# main_2_0.net
KiCad netlist of a schematic drawn in EAGLE
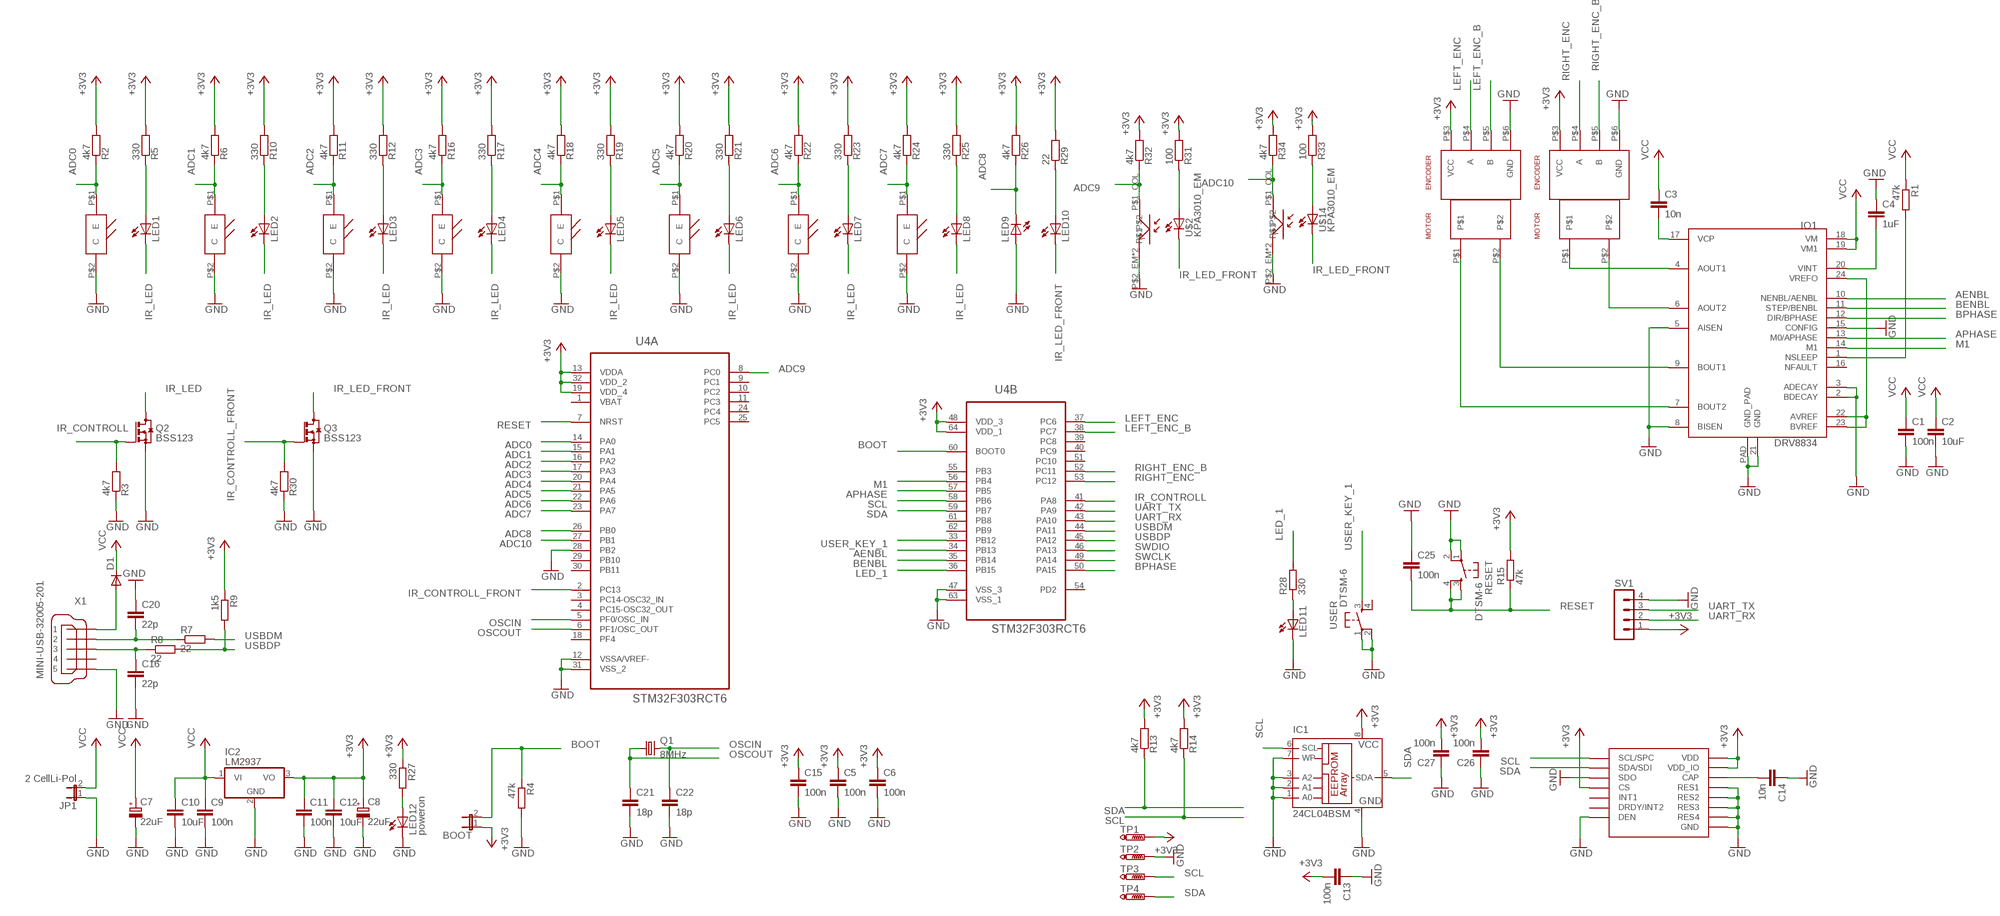
[diagram p0: schematic, sheet 1]

(export (version "E")
  (design (tool "Eeschema 10.0.6"))
  (components
    (comp (ref "BOOT")
      (value "JP1E")
      (footprint "eagle-import:JP1")
      (libsource (lib "eagle-import") (part "JP1E"))
    )
    (comp (ref "C1")
      (value "100n")
      (footprint "eagle-import:C1206")
      (libsource (lib "eagle-import") (part "C-EUC1206"))
    )
    (comp (ref "C2")
      (value "10uF")
      (footprint "eagle-import:C1206")
      (libsource (lib "eagle-import") (part "C-EUC1206"))
    )
    (comp (ref "C3")
      (value "10n")
      (footprint "eagle-import:C1206")
      (libsource (lib "eagle-import") (part "C-EUC1206"))
    )
    (comp (ref "C4")
      (value "1uF")
      (footprint "eagle-import:C1206")
      (libsource (lib "eagle-import") (part "C-EUC1206"))
    )
    (comp (ref "C5")
      (value "100n")
      (footprint "eagle-import:C0805")
      (libsource (lib "eagle-import") (part "C-EUC0805"))
    )
    (comp (ref "C6")
      (value "100n")
      (footprint "eagle-import:C0805")
      (libsource (lib "eagle-import") (part "C-EUC0805"))
    )
    (comp (ref "C7")
      (value "22uF")
      (footprint "eagle-import:153CLV-0505")
      (libsource (lib "eagle-import") (part "CPOL-EU153CLV-0505"))
    )
    (comp (ref "C8")
      (value "22uF")
      (footprint "eagle-import:153CLV-0505")
      (libsource (lib "eagle-import") (part "CPOL-EU153CLV-0505"))
    )
    (comp (ref "C9")
      (value "100n")
      (footprint "eagle-import:C0805")
      (libsource (lib "eagle-import") (part "C-EUC0805"))
    )
    (comp (ref "C10")
      (value "10uF")
      (footprint "eagle-import:C0805")
      (libsource (lib "eagle-import") (part "C-EUC0805"))
    )
    (comp (ref "C11")
      (value "100n")
      (footprint "eagle-import:C0805")
      (libsource (lib "eagle-import") (part "C-EUC0805"))
    )
    (comp (ref "C12")
      (value "10uF")
      (footprint "eagle-import:C0805")
      (libsource (lib "eagle-import") (part "C-EUC0805"))
    )
    (comp (ref "C13")
      (value "100n")
      (footprint "eagle-import:C0805")
      (libsource (lib "eagle-import") (part "C-EUC0805"))
    )
    (comp (ref "C14")
      (value "10n")
      (footprint "eagle-import:C0805")
      (libsource (lib "eagle-import") (part "C-EUC0805"))
    )
    (comp (ref "C15")
      (value "100n")
      (footprint "eagle-import:C0805")
      (libsource (lib "eagle-import") (part "C-EUC0805"))
    )
    (comp (ref "C16")
      (value "22p")
      (footprint "eagle-import:C0805")
      (libsource (lib "eagle-import") (part "C-EUC0805"))
    )
    (comp (ref "C20")
      (value "22p")
      (footprint "eagle-import:C0805")
      (libsource (lib "eagle-import") (part "C-EUC0805"))
    )
    (comp (ref "C21")
      (value "18p")
      (footprint "eagle-import:C0805")
      (libsource (lib "eagle-import") (part "C-EUC0805"))
    )
    (comp (ref "C22")
      (value "18p")
      (footprint "eagle-import:C0805")
      (libsource (lib "eagle-import") (part "C-EUC0805"))
    )
    (comp (ref "C25")
      (value "100n")
      (footprint "eagle-import:C0805")
      (libsource (lib "eagle-import") (part "C-EUC0805"))
    )
    (comp (ref "C26")
      (value "100n")
      (footprint "eagle-import:C0805")
      (libsource (lib "eagle-import") (part "C-EUC0805"))
    )
    (comp (ref "C27")
      (value "100n")
      (footprint "eagle-import:C0805")
      (libsource (lib "eagle-import") (part "C-EUC0805"))
    )
    (comp (ref "D1")
      (value "DIODE-SMB")
      (footprint "eagle-import:SMB")
      (libsource (lib "eagle-import") (part "DIODE-SMB"))
    )
    (comp (ref "IC1")
      (value "24CL04BSM")
      (footprint "eagle-import:SO-08M")
      (fields (field (name "MPN") "FM24CL04-S"))
      (libsource (lib "eagle-import") (part "24SMCL04B"))
    )
    (comp (ref "IC2")
      (value "LM2937")
      (footprint "eagle-import:TO263-3")
      (libsource (lib "eagle-import") (part "LM2937"))
    )
    (comp (ref "IO1")
      (value "DRV8834")
      (footprint "eagle-import:DRV8834_PCK")
      (libsource (lib "eagle-import") (part "DRV8834"))
    )
    (comp (ref "JP1")
      (value "2 CellLi-Pol")
      (footprint "eagle-import:JP1")
      (libsource (lib "eagle-import") (part "JP1E"))
    )
    (comp (ref "LED1")
      (value "LEDCHIPLED_1206")
      (footprint "eagle-import:CHIPLED_1206")
      (libsource (lib "eagle-import") (part "LEDCHIPLED_1206"))
    )
    (comp (ref "LED2")
      (value "LEDCHIPLED_1206")
      (footprint "eagle-import:CHIPLED_1206")
      (libsource (lib "eagle-import") (part "LEDCHIPLED_1206"))
    )
    (comp (ref "LED3")
      (value "LEDCHIPLED_1206")
      (footprint "eagle-import:CHIPLED_1206")
      (libsource (lib "eagle-import") (part "LEDCHIPLED_1206"))
    )
    (comp (ref "LED4")
      (value "LEDCHIPLED_1206")
      (footprint "eagle-import:CHIPLED_1206")
      (libsource (lib "eagle-import") (part "LEDCHIPLED_1206"))
    )
    (comp (ref "LED5")
      (value "LEDCHIPLED_1206")
      (footprint "eagle-import:CHIPLED_1206")
      (libsource (lib "eagle-import") (part "LEDCHIPLED_1206"))
    )
    (comp (ref "LED6")
      (value "LEDCHIPLED_1206")
      (footprint "eagle-import:CHIPLED_1206")
      (libsource (lib "eagle-import") (part "LEDCHIPLED_1206"))
    )
    (comp (ref "LED7")
      (value "LEDCHIPLED_1206")
      (footprint "eagle-import:CHIPLED_1206")
      (libsource (lib "eagle-import") (part "LEDCHIPLED_1206"))
    )
    (comp (ref "LED8")
      (value "LEDCHIPLED_1206")
      (footprint "eagle-import:CHIPLED_1206")
      (libsource (lib "eagle-import") (part "LEDCHIPLED_1206"))
    )
    (comp (ref "LED9")
      (value "LED5MM")
      (footprint "eagle-import:LED5MM")
      (libsource (lib "eagle-import") (part "my_parts_LED5MM"))
    )
    (comp (ref "LED10")
      (value "LED5MM")
      (footprint "eagle-import:LED5MM")
      (libsource (lib "eagle-import") (part "my_parts_LED5MM"))
    )
    (comp (ref "LED11")
      (value "LEDCHIPLED_1206")
      (footprint "eagle-import:CHIPLED_1206")
      (libsource (lib "eagle-import") (part "LEDCHIPLED_1206"))
    )
    (comp (ref "LED12")
      (value "poweron")
      (footprint "eagle-import:CHIPLED_1206")
      (libsource (lib "eagle-import") (part "LEDCHIPLED_1206"))
    )
    (comp (ref "LSM6DS0")
      (value "L3GD20H")
      (footprint "eagle-import:LGA16L")
      (libsource (lib "eagle-import") (part "L3GD20H"))
    )
    (comp (ref "Q1")
      (value "8MHz")
      (footprint "eagle-import:CTS406")
      (libsource (lib "eagle-import") (part "CRYSTALCTS406"))
    )
    (comp (ref "Q2")
      (value "BSS123")
      (footprint "eagle-import:SOT23")
      (libsource (lib "eagle-import") (part "BSS123"))
    )
    (comp (ref "Q3")
      (value "BSS123")
      (footprint "eagle-import:SOT23")
      (libsource (lib "eagle-import") (part "BSS123"))
    )
    (comp (ref "R1")
      (value "47k")
      (footprint "eagle-import:M1206")
      (libsource (lib "eagle-import") (part "R-EU_M1206"))
    )
    (comp (ref "R2")
      (value "4k7")
      (footprint "eagle-import:M0805")
      (libsource (lib "eagle-import") (part "R-EU_M0805"))
    )
    (comp (ref "R3")
      (value "4k7")
      (footprint "eagle-import:M0805")
      (libsource (lib "eagle-import") (part "R-EU_M0805"))
    )
    (comp (ref "R4")
      (value "47k")
      (footprint "eagle-import:M0805")
      (libsource (lib "eagle-import") (part "R-EU_M0805"))
    )
    (comp (ref "R5")
      (value "330")
      (footprint "eagle-import:M0805")
      (libsource (lib "eagle-import") (part "R-EU_M0805"))
    )
    (comp (ref "R6")
      (value "4k7")
      (footprint "eagle-import:M0805")
      (libsource (lib "eagle-import") (part "R-EU_M0805"))
    )
    (comp (ref "R7")
      (value "22")
      (footprint "eagle-import:M0805")
      (libsource (lib "eagle-import") (part "R-EU_M0805"))
    )
    (comp (ref "R8")
      (value "22")
      (footprint "eagle-import:M0805")
      (libsource (lib "eagle-import") (part "R-EU_M0805"))
    )
    (comp (ref "R9")
      (value "1k5")
      (footprint "eagle-import:M0805")
      (libsource (lib "eagle-import") (part "R-EU_M0805"))
    )
    (comp (ref "R10")
      (value "330")
      (footprint "eagle-import:M0805")
      (libsource (lib "eagle-import") (part "R-EU_M0805"))
    )
    (comp (ref "R11")
      (value "4k7")
      (footprint "eagle-import:M0805")
      (libsource (lib "eagle-import") (part "R-EU_M0805"))
    )
    (comp (ref "R12")
      (value "330")
      (footprint "eagle-import:M0805")
      (libsource (lib "eagle-import") (part "R-EU_M0805"))
    )
    (comp (ref "R13")
      (value "4k7")
      (footprint "eagle-import:M0805")
      (libsource (lib "eagle-import") (part "R-EU_M0805"))
    )
    (comp (ref "R14")
      (value "4k7")
      (footprint "eagle-import:M0805")
      (libsource (lib "eagle-import") (part "R-EU_M0805"))
    )
    (comp (ref "R15")
      (value "47k")
      (footprint "eagle-import:M0805")
      (libsource (lib "eagle-import") (part "R-EU_M0805"))
    )
    (comp (ref "R16")
      (value "4k7")
      (footprint "eagle-import:M0805")
      (libsource (lib "eagle-import") (part "R-EU_M0805"))
    )
    (comp (ref "R17")
      (value "330")
      (footprint "eagle-import:M0805")
      (libsource (lib "eagle-import") (part "R-EU_M0805"))
    )
    (comp (ref "R18")
      (value "4k7")
      (footprint "eagle-import:M0805")
      (libsource (lib "eagle-import") (part "R-EU_M0805"))
    )
    (comp (ref "R19")
      (value "330")
      (footprint "eagle-import:M0805")
      (libsource (lib "eagle-import") (part "R-EU_M0805"))
    )
    (comp (ref "R20")
      (value "4k7")
      (footprint "eagle-import:M0805")
      (libsource (lib "eagle-import") (part "R-EU_M0805"))
    )
    (comp (ref "R21")
      (value "330")
      (footprint "eagle-import:M0805")
      (libsource (lib "eagle-import") (part "R-EU_M0805"))
    )
    (comp (ref "R22")
      (value "4k7")
      (footprint "eagle-import:M0805")
      (libsource (lib "eagle-import") (part "R-EU_M0805"))
    )
    (comp (ref "R23")
      (value "330")
      (footprint "eagle-import:M0805")
      (libsource (lib "eagle-import") (part "R-EU_M0805"))
    )
    (comp (ref "R24")
      (value "4k7")
      (footprint "eagle-import:M0805")
      (libsource (lib "eagle-import") (part "R-EU_M0805"))
    )
    (comp (ref "R25")
      (value "330")
      (footprint "eagle-import:M0805")
      (libsource (lib "eagle-import") (part "R-EU_M0805"))
    )
    (comp (ref "R26")
      (value "4k7")
      (footprint "eagle-import:M0805")
      (libsource (lib "eagle-import") (part "R-EU_M0805"))
    )
    (comp (ref "R27")
      (value "330")
      (footprint "eagle-import:M0805")
      (libsource (lib "eagle-import") (part "R-EU_M0805"))
    )
    (comp (ref "R28")
      (value "330")
      (footprint "eagle-import:M0805")
      (libsource (lib "eagle-import") (part "R-EU_M0805"))
    )
    (comp (ref "R29")
      (value "22")
      (footprint "eagle-import:M0805")
      (libsource (lib "eagle-import") (part "R-EU_M0805"))
    )
    (comp (ref "R30")
      (value "4k7")
      (footprint "eagle-import:M0805")
      (libsource (lib "eagle-import") (part "R-EU_M0805"))
    )
    (comp (ref "R31")
      (value "100")
      (footprint "eagle-import:M0805")
      (libsource (lib "eagle-import") (part "R-EU_M0805"))
    )
    (comp (ref "R32")
      (value "4k7")
      (footprint "eagle-import:M0805")
      (libsource (lib "eagle-import") (part "R-EU_M0805"))
    )
    (comp (ref "R33")
      (value "100")
      (footprint "eagle-import:M0805")
      (libsource (lib "eagle-import") (part "R-EU_M0805"))
    )
    (comp (ref "R34")
      (value "4k7")
      (footprint "eagle-import:M0805")
      (libsource (lib "eagle-import") (part "R-EU_M0805"))
    )
    (comp (ref "RESET")
      (value "DTSM-6")
      (footprint "eagle-import:DTSM-6")
      (libsource (lib "eagle-import") (part "DTSM-6"))
    )
    (comp (ref "SV1")
      (value "MA04-1")
      (footprint "eagle-import:MA04-1")
      (libsource (lib "eagle-import") (part "MA04-1"))
    )
    (comp (ref "TP1")
      (value "PTR1B1,27")
      (footprint "eagle-import:B1,27")
      (libsource (lib "eagle-import") (part "PTR1B1,27"))
    )
    (comp (ref "TP2")
      (value "PTR1B1,27")
      (footprint "eagle-import:B1,27")
      (libsource (lib "eagle-import") (part "PTR1B1,27"))
    )
    (comp (ref "TP3")
      (value "PTR1B1,27")
      (footprint "eagle-import:B1,27")
      (libsource (lib "eagle-import") (part "PTR1B1,27"))
    )
    (comp (ref "TP4")
      (value "PTR1B1,27")
      (footprint "eagle-import:B1,27")
      (libsource (lib "eagle-import") (part "PTR1B1,27"))
    )
    (comp (ref "U$1")
      (value "KPA3010")
      (footprint "eagle-import:KPA3010")
      (libsource (lib "eagle-import") (part "KPA3010"))
    )
    (comp (ref "U$2")
      (value "KPA3010_EM")
      (footprint "eagle-import:KPA3010")
      (libsource (lib "eagle-import") (part "KPA3010_EM"))
    )
    (comp (ref "U$3")
      (value "SFH3710")
      (footprint "eagle-import:SFH3710")
      (libsource (lib "eagle-import") (part "SFH3710"))
    )
    (comp (ref "U$4")
      (value "SFH3710")
      (footprint "eagle-import:SFH3710")
      (libsource (lib "eagle-import") (part "SFH3710"))
    )
    (comp (ref "U$5")
      (value "SFH3710")
      (footprint "eagle-import:SFH3710")
      (libsource (lib "eagle-import") (part "SFH3710"))
    )
    (comp (ref "U$6")
      (value "SFH3710")
      (footprint "eagle-import:SFH3710")
      (libsource (lib "eagle-import") (part "SFH3710"))
    )
    (comp (ref "U$7")
      (value "SFH3710")
      (footprint "eagle-import:SFH3710")
      (libsource (lib "eagle-import") (part "SFH3710"))
    )
    (comp (ref "U$8")
      (value "SFH3710")
      (footprint "eagle-import:SFH3710")
      (libsource (lib "eagle-import") (part "SFH3710"))
    )
    (comp (ref "U$9")
      (value "SFH3710")
      (footprint "eagle-import:SFH3710")
      (libsource (lib "eagle-import") (part "SFH3710"))
    )
    (comp (ref "U$10")
      (value "SFH3710")
      (footprint "eagle-import:SFH3710")
      (libsource (lib "eagle-import") (part "SFH3710"))
    )
    (comp (ref "U$11")
      (value "POLOLU_GEAR_MOTORPOLO")
      (footprint "eagle-import:POLOLU_GEAR_MOTOR")
      (libsource (lib "eagle-import") (part "POLOLU_GEAR_MOTORPOLO"))
    )
    (comp (ref "U$12")
      (value "POLOLU_GEAR_MOTORPOLO")
      (footprint "eagle-import:POLOLU_GEAR_MOTOR")
      (libsource (lib "eagle-import") (part "POLOLU_GEAR_MOTORPOLO"))
    )
    (comp (ref "U$13")
      (value "KPA3010")
      (footprint "eagle-import:KPA3010")
      (libsource (lib "eagle-import") (part "KPA3010"))
    )
    (comp (ref "U$14")
      (value "KPA3010_EM")
      (footprint "eagle-import:KPA3010")
      (libsource (lib "eagle-import") (part "KPA3010_EM"))
    )
    (comp (ref "U4")
      (value "STM32F303RCT6")
      (footprint "eagle-import:QFP50P1200X1200X160-64N")
      (libsource (lib "eagle-import") (part "STM32F303RCT6"))
    )
    (comp (ref "USER")
      (value "DTSM-6")
      (footprint "eagle-import:DTSM-6")
      (libsource (lib "eagle-import") (part "DTSM-6"))
    )
    (comp (ref "X1")
      (value "MINI-USB-32005-201")
      (footprint "eagle-import:32005-201")
      (libsource (lib "eagle-import") (part "MINI-USB-32005-201"))
    )
  )
  (nets
    (net (code "1") (name "+3V3") (class "Default")
      (node (ref "BOOT") (pin "1") (pinfunction "1_1") (pintype "passive"))
      (node (ref "C11") (pin "1") (pinfunction "1_1") (pintype "passive"))
      (node (ref "C12") (pin "1") (pinfunction "1_1") (pintype "passive"))
      (node (ref "C13") (pin "2") (pinfunction "2_2") (pintype "passive"))
      (node (ref "C15") (pin "1") (pinfunction "1_1") (pintype "passive"))
      (node (ref "C26") (pin "2") (pinfunction "2_2") (pintype "passive"))
      (node (ref "C27") (pin "2") (pinfunction "2_2") (pintype "passive"))
      (node (ref "C5") (pin "1") (pinfunction "1_1") (pintype "passive"))
      (node (ref "C6") (pin "1") (pinfunction "1_1") (pintype "passive"))
      (node (ref "C8") (pin "+") (pinfunction "+_+") (pintype "passive"))
      (node (ref "IC1") (pin "8") (pinfunction "VCC_8") (pintype "power_in"))
      (node (ref "IC2") (pin "3") (pinfunction "VO_3") (pintype "passive"))
      (node (ref "LSM6DS0") (pin "P$1") (pinfunction "VDD_IO_P$1") (pintype "power_in"))
      (node (ref "LSM6DS0") (pin "P$16") (pinfunction "VDD_P$16") (pintype "power_in"))
      (node (ref "LSM6DS0") (pin "P$5") (pinfunction "CS_P$5") (pintype "bidirectional"))
      (node (ref "R10") (pin "2") (pinfunction "2_2") (pintype "passive"))
      (node (ref "R11") (pin "2") (pinfunction "2_2") (pintype "passive"))
      (node (ref "R12") (pin "2") (pinfunction "2_2") (pintype "passive"))
      (node (ref "R13") (pin "2") (pinfunction "2_2") (pintype "passive"))
      (node (ref "R14") (pin "2") (pinfunction "2_2") (pintype "passive"))
      (node (ref "R15") (pin "2") (pinfunction "2_2") (pintype "passive"))
      (node (ref "R16") (pin "2") (pinfunction "2_2") (pintype "passive"))
      (node (ref "R17") (pin "2") (pinfunction "2_2") (pintype "passive"))
      (node (ref "R18") (pin "2") (pinfunction "2_2") (pintype "passive"))
      (node (ref "R19") (pin "2") (pinfunction "2_2") (pintype "passive"))
      (node (ref "R2") (pin "2") (pinfunction "2_2") (pintype "passive"))
      (node (ref "R20") (pin "2") (pinfunction "2_2") (pintype "passive"))
      (node (ref "R21") (pin "2") (pinfunction "2_2") (pintype "passive"))
      (node (ref "R22") (pin "2") (pinfunction "2_2") (pintype "passive"))
      (node (ref "R23") (pin "2") (pinfunction "2_2") (pintype "passive"))
      (node (ref "R24") (pin "2") (pinfunction "2_2") (pintype "passive"))
      (node (ref "R25") (pin "2") (pinfunction "2_2") (pintype "passive"))
      (node (ref "R26") (pin "2") (pinfunction "2_2") (pintype "passive"))
      (node (ref "R27") (pin "1") (pinfunction "1_1") (pintype "passive"))
      (node (ref "R29") (pin "2") (pinfunction "2_2") (pintype "passive"))
      (node (ref "R31") (pin "2") (pinfunction "2_2") (pintype "passive"))
      (node (ref "R32") (pin "2") (pinfunction "2_2") (pintype "passive"))
      (node (ref "R33") (pin "2") (pinfunction "2_2") (pintype "passive"))
      (node (ref "R34") (pin "2") (pinfunction "2_2") (pintype "passive"))
      (node (ref "R5") (pin "2") (pinfunction "2_2") (pintype "passive"))
      (node (ref "R6") (pin "2") (pinfunction "2_2") (pintype "passive"))
      (node (ref "R9") (pin "1") (pinfunction "1_1") (pintype "passive"))
      (node (ref "SV1") (pin "1") (pinfunction "1_1") (pintype "passive"))
      (node (ref "TP1") (pin "TP") (pinfunction "TP_TP") (pintype "input"))
      (node (ref "U$11") (pin "P$3") (pinfunction "VCC_P$3") (pintype "bidirectional"))
      (node (ref "U$12") (pin "P$3") (pinfunction "VCC_P$3") (pintype "bidirectional"))
      (node (ref "U4") (pin "13") (pinfunction "VDDA_13") (pintype "power_in"))
      (node (ref "U4") (pin "19") (pinfunction "VDD_4_19") (pintype "power_in"))
      (node (ref "U4") (pin "32") (pinfunction "VDD_2_32") (pintype "power_in"))
      (node (ref "U4") (pin "48") (pinfunction "VDD_3_48") (pintype "power_in"))
      (node (ref "U4") (pin "64") (pinfunction "VDD_1_64") (pintype "power_in"))
    )
    (net (code "2") (name "/ADC0") (class "Default")
      (node (ref "R2") (pin "1") (pinfunction "1_1") (pintype "passive"))
      (node (ref "U$3") (pin "P$1") (pinfunction "E_P$1") (pintype "bidirectional"))
      (node (ref "U4") (pin "14") (pinfunction "PA0_14") (pintype "bidirectional"))
    )
    (net (code "3") (name "/ADC1") (class "Default")
      (node (ref "R6") (pin "1") (pinfunction "1_1") (pintype "passive"))
      (node (ref "U$4") (pin "P$1") (pinfunction "E_P$1") (pintype "bidirectional"))
      (node (ref "U4") (pin "15") (pinfunction "PA1_15") (pintype "bidirectional"))
    )
    (net (code "4") (name "/ADC2") (class "Default")
      (node (ref "R11") (pin "1") (pinfunction "1_1") (pintype "passive"))
      (node (ref "U$5") (pin "P$1") (pinfunction "E_P$1") (pintype "bidirectional"))
      (node (ref "U4") (pin "16") (pinfunction "PA2_16") (pintype "bidirectional"))
    )
    (net (code "5") (name "/ADC3") (class "Default")
      (node (ref "R16") (pin "1") (pinfunction "1_1") (pintype "passive"))
      (node (ref "U$6") (pin "P$1") (pinfunction "E_P$1") (pintype "bidirectional"))
      (node (ref "U4") (pin "17") (pinfunction "PA3_17") (pintype "bidirectional"))
    )
    (net (code "6") (name "/ADC4") (class "Default")
      (node (ref "R18") (pin "1") (pinfunction "1_1") (pintype "passive"))
      (node (ref "U$7") (pin "P$1") (pinfunction "E_P$1") (pintype "bidirectional"))
      (node (ref "U4") (pin "20") (pinfunction "PA4_20") (pintype "bidirectional"))
    )
    (net (code "7") (name "/ADC5") (class "Default")
      (node (ref "R20") (pin "1") (pinfunction "1_1") (pintype "passive"))
      (node (ref "U$8") (pin "P$1") (pinfunction "E_P$1") (pintype "bidirectional"))
      (node (ref "U4") (pin "21") (pinfunction "PA5_21") (pintype "bidirectional"))
    )
    (net (code "8") (name "/ADC6") (class "Default")
      (node (ref "R22") (pin "1") (pinfunction "1_1") (pintype "passive"))
      (node (ref "U$9") (pin "P$1") (pinfunction "E_P$1") (pintype "bidirectional"))
      (node (ref "U4") (pin "22") (pinfunction "PA6_22") (pintype "bidirectional"))
    )
    (net (code "9") (name "/ADC7") (class "Default")
      (node (ref "R24") (pin "1") (pinfunction "1_1") (pintype "passive"))
      (node (ref "U$10") (pin "P$1") (pinfunction "E_P$1") (pintype "bidirectional"))
      (node (ref "U4") (pin "23") (pinfunction "PA7_23") (pintype "bidirectional"))
    )
    (net (code "10") (name "/ADC8") (class "Default")
      (node (ref "LED9") (pin "K") (pinfunction "C_K") (pintype "passive"))
      (node (ref "R26") (pin "1") (pinfunction "1_1") (pintype "passive"))
      (node (ref "U4") (pin "26") (pinfunction "PB0_26") (pintype "bidirectional"))
    )
    (net (code "11") (name "/ADC9") (class "Default")
      (node (ref "R32") (pin "1") (pinfunction "1_1") (pintype "passive"))
      (node (ref "U$1") (pin "P$1_COL") (pinfunction "P$1_P$1_COL") (pintype "bidirectional"))
      (node (ref "U4") (pin "8") (pinfunction "PC0_8") (pintype "bidirectional"))
    )
    (net (code "12") (name "/ADC10") (class "Default")
      (node (ref "R34") (pin "1") (pinfunction "1_1") (pintype "passive"))
      (node (ref "U$13") (pin "P$1_COL") (pinfunction "P$1_P$1_COL") (pintype "bidirectional"))
      (node (ref "U4") (pin "27") (pinfunction "PB1_27") (pintype "bidirectional"))
    )
    (net (code "13") (name "/AENBL") (class "Default")
      (node (ref "IO1") (pin "10") (pinfunction "NENBL/AENBL_10") (pintype "bidirectional"))
      (node (ref "U4") (pin "34") (pinfunction "PB13_34") (pintype "bidirectional"))
    )
    (net (code "14") (name "/APHASE") (class "Default")
      (node (ref "IO1") (pin "13") (pinfunction "M0/APHASE_13") (pintype "bidirectional"))
      (node (ref "U4") (pin "57") (pinfunction "PB5_57") (pintype "bidirectional"))
    )
    (net (code "15") (name "/BENBL") (class "Default")
      (node (ref "IO1") (pin "11") (pinfunction "STEP/BENBL_11") (pintype "bidirectional"))
      (node (ref "U4") (pin "35") (pinfunction "PB14_35") (pintype "bidirectional"))
    )
    (net (code "16") (name "/BOOT") (class "Default")
      (node (ref "BOOT") (pin "2") (pinfunction "2_2") (pintype "passive"))
      (node (ref "R4") (pin "1") (pinfunction "1_1") (pintype "passive"))
      (node (ref "U4") (pin "60") (pinfunction "BOOT0_60") (pintype "input"))
    )
    (net (code "17") (name "/BPHASE") (class "Default")
      (node (ref "IO1") (pin "12") (pinfunction "DIR/BPHASE_12") (pintype "bidirectional"))
      (node (ref "U4") (pin "50") (pinfunction "PA15_50") (pintype "bidirectional"))
    )
    (net (code "18") (name "/IR_CONTROLL") (class "Default")
      (node (ref "Q2") (pin "1") (pinfunction "G_1") (pintype "passive"))
      (node (ref "R3") (pin "2") (pinfunction "2_2") (pintype "passive"))
      (node (ref "U4") (pin "41") (pinfunction "PA8_41") (pintype "bidirectional"))
    )
    (net (code "19") (name "/IR_CONTROLL_FRONT") (class "Default")
      (node (ref "Q3") (pin "1") (pinfunction "G_1") (pintype "passive"))
      (node (ref "R30") (pin "2") (pinfunction "2_2") (pintype "passive"))
      (node (ref "U4") (pin "2") (pinfunction "PC13_2") (pintype "bidirectional"))
    )
    (net (code "20") (name "/IR_LED") (class "Default")
      (node (ref "LED1") (pin "C") (pinfunction "C_C") (pintype "passive"))
      (node (ref "LED2") (pin "C") (pinfunction "C_C") (pintype "passive"))
      (node (ref "LED3") (pin "C") (pinfunction "C_C") (pintype "passive"))
      (node (ref "LED4") (pin "C") (pinfunction "C_C") (pintype "passive"))
      (node (ref "LED5") (pin "C") (pinfunction "C_C") (pintype "passive"))
      (node (ref "LED6") (pin "C") (pinfunction "C_C") (pintype "passive"))
      (node (ref "LED7") (pin "C") (pinfunction "C_C") (pintype "passive"))
      (node (ref "LED8") (pin "C") (pinfunction "C_C") (pintype "passive"))
      (node (ref "Q2") (pin "3") (pinfunction "D_3") (pintype "passive"))
    )
    (net (code "21") (name "/IR_LED_FRONT") (class "Default")
      (node (ref "LED10") (pin "K") (pinfunction "C_K") (pintype "passive"))
      (node (ref "Q3") (pin "3") (pinfunction "D_3") (pintype "passive"))
      (node (ref "U$14") (pin "P$1_COL") (pinfunction "C_P$1_COL") (pintype "passive"))
      (node (ref "U$2") (pin "P$1_COL") (pinfunction "C_P$1_COL") (pintype "passive"))
    )
    (net (code "22") (name "/LED_1") (class "Default")
      (node (ref "R28") (pin "2") (pinfunction "2_2") (pintype "passive"))
      (node (ref "U4") (pin "36") (pinfunction "PB15_36") (pintype "bidirectional"))
    )
    (net (code "23") (name "/LEFT_ENC") (class "Default")
      (node (ref "U$11") (pin "P$4") (pinfunction "A_P$4") (pintype "bidirectional"))
      (node (ref "U4") (pin "37") (pinfunction "PC6_37") (pintype "bidirectional"))
    )
    (net (code "24") (name "/LEFT_ENC_B") (class "Default")
      (node (ref "U$11") (pin "P$5") (pinfunction "B_P$5") (pintype "bidirectional"))
      (node (ref "U4") (pin "38") (pinfunction "PC7_38") (pintype "bidirectional"))
    )
    (net (code "25") (name "/M1") (class "Default")
      (node (ref "IO1") (pin "14") (pinfunction "M1_14") (pintype "bidirectional"))
      (node (ref "U4") (pin "56") (pinfunction "PB4_56") (pintype "bidirectional"))
    )
    (net (code "26") (name "/OSCIN") (class "Default")
      (node (ref "C22") (pin "1") (pinfunction "1_1") (pintype "passive"))
      (node (ref "Q1") (pin "3") (pinfunction "2_3") (pintype "passive"))
      (node (ref "U4") (pin "5") (pinfunction "PF0/OSC_IN_5") (pintype "bidirectional"))
    )
    (net (code "27") (name "/OSCOUT") (class "Default")
      (node (ref "C21") (pin "1") (pinfunction "1_1") (pintype "passive"))
      (node (ref "Q1") (pin "1") (pinfunction "1_1") (pintype "passive"))
      (node (ref "U4") (pin "6") (pinfunction "PF1/OSC_OUT_6") (pintype "bidirectional"))
    )
    (net (code "28") (name "/RESET") (class "Default")
      (node (ref "C25") (pin "2") (pinfunction "2_2") (pintype "passive"))
      (node (ref "R15") (pin "1") (pinfunction "1_1") (pintype "passive"))
      (node (ref "RESET") (pin "3") (pinfunction "3_3") (pintype "passive"))
      (node (ref "RESET") (pin "4") (pinfunction "4_4") (pintype "passive"))
      (node (ref "U4") (pin "7") (pinfunction "NRST_7") (pintype "bidirectional"))
    )
    (net (code "29") (name "/RIGHT_ENC") (class "Default")
      (node (ref "U$12") (pin "P$4") (pinfunction "A_P$4") (pintype "bidirectional"))
      (node (ref "U4") (pin "53") (pinfunction "PC12_53") (pintype "bidirectional"))
    )
    (net (code "30") (name "/RIGHT_ENC_B") (class "Default")
      (node (ref "U$12") (pin "P$5") (pinfunction "B_P$5") (pintype "bidirectional"))
      (node (ref "U4") (pin "52") (pinfunction "PC11_52") (pintype "bidirectional"))
    )
    (net (code "31") (name "/SCL") (class "Default")
      (node (ref "IC1") (pin "6") (pinfunction "SCL_6") (pintype "input"))
      (node (ref "LSM6DS0") (pin "P$2") (pinfunction "SCL/SPC_P$2") (pintype "bidirectional"))
      (node (ref "R14") (pin "1") (pinfunction "1_1") (pintype "passive"))
      (node (ref "TP3") (pin "TP") (pinfunction "TP_TP") (pintype "input"))
      (node (ref "U4") (pin "58") (pinfunction "PB6_58") (pintype "bidirectional"))
    )
    (net (code "32") (name "/SDA") (class "Default")
      (node (ref "IC1") (pin "5") (pinfunction "SDA_5") (pintype "bidirectional"))
      (node (ref "LSM6DS0") (pin "P$3") (pinfunction "SDA/SDI_P$3") (pintype "bidirectional"))
      (node (ref "R13") (pin "1") (pinfunction "1_1") (pintype "passive"))
      (node (ref "TP4") (pin "TP") (pinfunction "TP_TP") (pintype "input"))
      (node (ref "U4") (pin "59") (pinfunction "PB7_59") (pintype "bidirectional"))
    )
    (net (code "33") (name "/SWCLK") (class "Default")
      (node (ref "U4") (pin "49") (pinfunction "PA14_49") (pintype "bidirectional"))
    )
    (net (code "34") (name "/SWDIO") (class "Default")
      (node (ref "U4") (pin "46") (pinfunction "PA13_46") (pintype "bidirectional"))
    )
    (net (code "35") (name "/UART_RX") (class "Default")
      (node (ref "SV1") (pin "2") (pinfunction "2_2") (pintype "passive"))
      (node (ref "U4") (pin "43") (pinfunction "PA10_43") (pintype "bidirectional"))
    )
    (net (code "36") (name "/UART_TX") (class "Default")
      (node (ref "SV1") (pin "3") (pinfunction "3_3") (pintype "passive"))
      (node (ref "U4") (pin "42") (pinfunction "PA9_42") (pintype "bidirectional"))
    )
    (net (code "37") (name "/USBDM") (class "Default")
      (node (ref "R7") (pin "2") (pinfunction "2_2") (pintype "passive"))
      (node (ref "U4") (pin "44") (pinfunction "PA11_44") (pintype "bidirectional"))
    )
    (net (code "38") (name "/USBDP") (class "Default")
      (node (ref "R8") (pin "2") (pinfunction "2_2") (pintype "passive"))
      (node (ref "R9") (pin "2") (pinfunction "2_2") (pintype "passive"))
      (node (ref "U4") (pin "45") (pinfunction "PA12_45") (pintype "bidirectional"))
    )
    (net (code "39") (name "/USER_KEY_1") (class "Default")
      (node (ref "U4") (pin "33") (pinfunction "PB12_33") (pintype "bidirectional"))
      (node (ref "USER") (pin "3") (pinfunction "3_3") (pintype "passive"))
    )
    (net (code "40") (name "/VBAT") (class "Default")
      (node (ref "U4") (pin "1") (pinfunction "VBAT_1") (pintype "power_in"))
    )
    (net (code "41") (name "GND") (class "Default")
      (node (ref "C1") (pin "2") (pinfunction "2_2") (pintype "passive"))
      (node (ref "C10") (pin "2") (pinfunction "2_2") (pintype "passive"))
      (node (ref "C11") (pin "2") (pinfunction "2_2") (pintype "passive"))
      (node (ref "C12") (pin "2") (pinfunction "2_2") (pintype "passive"))
      (node (ref "C13") (pin "1") (pinfunction "1_1") (pintype "passive"))
      (node (ref "C14") (pin "1") (pinfunction "1_1") (pintype "passive"))
      (node (ref "C15") (pin "2") (pinfunction "2_2") (pintype "passive"))
      (node (ref "C16") (pin "2") (pinfunction "2_2") (pintype "passive"))
      (node (ref "C2") (pin "2") (pinfunction "2_2") (pintype "passive"))
      (node (ref "C20") (pin "1") (pinfunction "1_1") (pintype "passive"))
      (node (ref "C21") (pin "2") (pinfunction "2_2") (pintype "passive"))
      (node (ref "C22") (pin "2") (pinfunction "2_2") (pintype "passive"))
      (node (ref "C25") (pin "1") (pinfunction "1_1") (pintype "passive"))
      (node (ref "C26") (pin "1") (pinfunction "1_1") (pintype "passive"))
      (node (ref "C27") (pin "1") (pinfunction "1_1") (pintype "passive"))
      (node (ref "C4") (pin "1") (pinfunction "1_1") (pintype "passive"))
      (node (ref "C5") (pin "2") (pinfunction "2_2") (pintype "passive"))
      (node (ref "C6") (pin "2") (pinfunction "2_2") (pintype "passive"))
      (node (ref "C7") (pin "-") (pinfunction "-_-") (pintype "passive"))
      (node (ref "C8") (pin "-") (pinfunction "-_-") (pintype "passive"))
      (node (ref "C9") (pin "2") (pinfunction "2_2") (pintype "passive"))
      (node (ref "IC1") (pin "1") (pinfunction "A0_1") (pintype "input"))
      (node (ref "IC1") (pin "2") (pinfunction "A1_2") (pintype "input"))
      (node (ref "IC1") (pin "3") (pinfunction "A2_3") (pintype "input"))
      (node (ref "IC1") (pin "4") (pinfunction "GND_4") (pintype "power_in"))
      (node (ref "IC1") (pin "7") (pinfunction "WP_7") (pintype "input"))
      (node (ref "IC2") (pin "2") (pinfunction "GND_2") (pintype "passive"))
      (node (ref "IO1") (pin "15") (pinfunction "CONFIG_15") (pintype "bidirectional"))
      (node (ref "IO1") (pin "2") (pinfunction "BDECAY_2") (pintype "bidirectional"))
      (node (ref "IO1") (pin "21") (pinfunction "GND_21") (pintype "bidirectional"))
      (node (ref "IO1") (pin "3") (pinfunction "ADECAY_3") (pintype "bidirectional"))
      (node (ref "IO1") (pin "5") (pinfunction "AISEN_5") (pintype "bidirectional"))
      (node (ref "IO1") (pin "8") (pinfunction "BISEN_8") (pintype "bidirectional"))
      (node (ref "IO1") (pin "PAD") (pinfunction "GND_PAD_PAD") (pintype "bidirectional"))
      (node (ref "JP1") (pin "1") (pinfunction "1_1") (pintype "passive"))
      (node (ref "LED11") (pin "C") (pinfunction "C_C") (pintype "passive"))
      (node (ref "LED12") (pin "C") (pinfunction "C_C") (pintype "passive"))
      (node (ref "LED9") (pin "A") (pinfunction "A_A") (pintype "passive"))
      (node (ref "LSM6DS0") (pin "P$10") (pinfunction "RES2_P$10") (pintype "bidirectional"))
      (node (ref "LSM6DS0") (pin "P$11") (pinfunction "RES3_P$11") (pintype "bidirectional"))
      (node (ref "LSM6DS0") (pin "P$12") (pinfunction "GND_P$12") (pintype "power_in"))
      (node (ref "LSM6DS0") (pin "P$13") (pinfunction "GND_P$13") (pintype "power_in"))
      (node (ref "LSM6DS0") (pin "P$15") (pinfunction "RES4_P$15") (pintype "bidirectional"))
      (node (ref "LSM6DS0") (pin "P$4") (pinfunction "SDO_P$4") (pintype "bidirectional"))
      (node (ref "LSM6DS0") (pin "P$8") (pinfunction "DEN_P$8") (pintype "bidirectional"))
      (node (ref "LSM6DS0") (pin "P$9") (pinfunction "RES1_P$9") (pintype "bidirectional"))
      (node (ref "Q2") (pin "2") (pinfunction "S_2") (pintype "passive"))
      (node (ref "Q3") (pin "2") (pinfunction "S_2") (pintype "passive"))
      (node (ref "R3") (pin "1") (pinfunction "1_1") (pintype "passive"))
      (node (ref "R30") (pin "1") (pinfunction "1_1") (pintype "passive"))
      (node (ref "R4") (pin "2") (pinfunction "2_2") (pintype "passive"))
      (node (ref "RESET") (pin "1") (pinfunction "1_1") (pintype "passive"))
      (node (ref "RESET") (pin "2") (pinfunction "2_2") (pintype "passive"))
      (node (ref "SV1") (pin "4") (pinfunction "4_4") (pintype "passive"))
      (node (ref "TP2") (pin "TP") (pinfunction "TP_TP") (pintype "input"))
      (node (ref "U$1") (pin "P$2_EM") (pinfunction "P$2_P$2_EM") (pintype "bidirectional"))
      (node (ref "U$1") (pin "P$3-NC") (pinfunction "P$2_P$3-NC") (pintype "bidirectional"))
      (node (ref "U$10") (pin "P$2") (pinfunction "C_P$2") (pintype "bidirectional"))
      (node (ref "U$11") (pin "P$6") (pinfunction "GND_P$6") (pintype "bidirectional"))
      (node (ref "U$12") (pin "P$6") (pinfunction "GND_P$6") (pintype "bidirectional"))
      (node (ref "U$13") (pin "P$2_EM") (pinfunction "P$2_P$2_EM") (pintype "bidirectional"))
      (node (ref "U$13") (pin "P$3-NC") (pinfunction "P$2_P$3-NC") (pintype "bidirectional"))
      (node (ref "U$3") (pin "P$2") (pinfunction "C_P$2") (pintype "bidirectional"))
      (node (ref "U$4") (pin "P$2") (pinfunction "C_P$2") (pintype "bidirectional"))
      (node (ref "U$5") (pin "P$2") (pinfunction "C_P$2") (pintype "bidirectional"))
      (node (ref "U$6") (pin "P$2") (pinfunction "C_P$2") (pintype "bidirectional"))
      (node (ref "U$7") (pin "P$2") (pinfunction "C_P$2") (pintype "bidirectional"))
      (node (ref "U$8") (pin "P$2") (pinfunction "C_P$2") (pintype "bidirectional"))
      (node (ref "U$9") (pin "P$2") (pinfunction "C_P$2") (pintype "bidirectional"))
      (node (ref "U4") (pin "12") (pinfunction "VSSA/VREF-_12") (pintype "power_in"))
      (node (ref "U4") (pin "28") (pinfunction "PB2_28") (pintype "bidirectional"))
      (node (ref "U4") (pin "31") (pinfunction "VSS_2_31") (pintype "passive"))
      (node (ref "U4") (pin "47") (pinfunction "VSS_3_47") (pintype "passive"))
      (node (ref "U4") (pin "63") (pinfunction "VSS_1_63") (pintype "passive"))
      (node (ref "USER") (pin "1") (pinfunction "1_1") (pintype "passive"))
      (node (ref "USER") (pin "2") (pinfunction "2_2") (pintype "passive"))
      (node (ref "X1") (pin "5") (pinfunction "5_5") (pintype "passive"))
    )
    (net (code "42") (name "Net-(C16-Pad1)") (class "Default")
      (node (ref "C16") (pin "1") (pinfunction "1_1") (pintype "passive"))
      (node (ref "R8") (pin "1") (pinfunction "1_1") (pintype "passive"))
      (node (ref "X1") (pin "3") (pinfunction "3_3") (pintype "passive"))
    )
    (net (code "43") (name "Net-(C20-Pad2)") (class "Default")
      (node (ref "C20") (pin "2") (pinfunction "2_2") (pintype "passive"))
      (node (ref "R7") (pin "1") (pinfunction "1_1") (pintype "passive"))
      (node (ref "X1") (pin "2") (pinfunction "2_2") (pintype "passive"))
    )
    (net (code "44") (name "Net-(D1-PadA)") (class "Default")
      (node (ref "D1") (pin "A") (pinfunction "A_A") (pintype "passive"))
      (node (ref "X1") (pin "1") (pinfunction "1_1") (pintype "passive"))
    )
    (net (code "45") (name "Net-(IO1-AOUT1)") (class "Default")
      (node (ref "IO1") (pin "4") (pinfunction "AOUT1_4") (pintype "bidirectional"))
      (node (ref "U$12") (pin "P$1") (pinfunction "P$1_P$1") (pintype "bidirectional"))
    )
    (net (code "46") (name "Net-(IO1-AOUT2)") (class "Default")
      (node (ref "IO1") (pin "6") (pinfunction "AOUT2_6") (pintype "bidirectional"))
      (node (ref "U$12") (pin "P$2") (pinfunction "P$2_P$2") (pintype "bidirectional"))
    )
    (net (code "47") (name "Net-(IO1-AVREF)") (class "Default")
      (node (ref "IO1") (pin "22") (pinfunction "AVREF_22") (pintype "bidirectional"))
      (node (ref "IO1") (pin "23") (pinfunction "BVREF_23") (pintype "bidirectional"))
      (node (ref "IO1") (pin "24") (pinfunction "VREFO_24") (pintype "bidirectional"))
    )
    (net (code "48") (name "Net-(IO1-BOUT1)") (class "Default")
      (node (ref "IO1") (pin "9") (pinfunction "BOUT1_9") (pintype "bidirectional"))
      (node (ref "U$11") (pin "P$2") (pinfunction "P$2_P$2") (pintype "bidirectional"))
    )
    (net (code "49") (name "Net-(IO1-BOUT2)") (class "Default")
      (node (ref "IO1") (pin "7") (pinfunction "BOUT2_7") (pintype "bidirectional"))
      (node (ref "U$11") (pin "P$1") (pinfunction "P$1_P$1") (pintype "bidirectional"))
    )
    (net (code "50") (name "Net-(IO1-NSLEEP)") (class "Default")
      (node (ref "IO1") (pin "1") (pinfunction "NSLEEP_1") (pintype "bidirectional"))
      (node (ref "R1") (pin "2") (pinfunction "2_2") (pintype "passive"))
    )
    (net (code "51") (name "Net-(IO1-VCP)") (class "Default")
      (node (ref "C3") (pin "2") (pinfunction "2_2") (pintype "passive"))
      (node (ref "IO1") (pin "17") (pinfunction "VCP_17") (pintype "bidirectional"))
    )
    (net (code "52") (name "Net-(IO1-VINT)") (class "Default")
      (node (ref "C4") (pin "2") (pinfunction "2_2") (pintype "passive"))
      (node (ref "IO1") (pin "20") (pinfunction "VINT_20") (pintype "bidirectional"))
    )
    (net (code "53") (name "Net-(LED1-PadA)") (class "Default")
      (node (ref "LED1") (pin "A") (pinfunction "A_A") (pintype "passive"))
      (node (ref "R5") (pin "1") (pinfunction "1_1") (pintype "passive"))
    )
    (net (code "54") (name "Net-(LED2-PadA)") (class "Default")
      (node (ref "LED2") (pin "A") (pinfunction "A_A") (pintype "passive"))
      (node (ref "R10") (pin "1") (pinfunction "1_1") (pintype "passive"))
    )
    (net (code "55") (name "Net-(LED3-PadA)") (class "Default")
      (node (ref "LED3") (pin "A") (pinfunction "A_A") (pintype "passive"))
      (node (ref "R12") (pin "1") (pinfunction "1_1") (pintype "passive"))
    )
    (net (code "56") (name "Net-(LED4-PadA)") (class "Default")
      (node (ref "LED4") (pin "A") (pinfunction "A_A") (pintype "passive"))
      (node (ref "R17") (pin "1") (pinfunction "1_1") (pintype "passive"))
    )
    (net (code "57") (name "Net-(LED5-PadA)") (class "Default")
      (node (ref "LED5") (pin "A") (pinfunction "A_A") (pintype "passive"))
      (node (ref "R19") (pin "1") (pinfunction "1_1") (pintype "passive"))
    )
    (net (code "58") (name "Net-(LED6-PadA)") (class "Default")
      (node (ref "LED6") (pin "A") (pinfunction "A_A") (pintype "passive"))
      (node (ref "R21") (pin "1") (pinfunction "1_1") (pintype "passive"))
    )
    (net (code "59") (name "Net-(LED7-PadA)") (class "Default")
      (node (ref "LED7") (pin "A") (pinfunction "A_A") (pintype "passive"))
      (node (ref "R23") (pin "1") (pinfunction "1_1") (pintype "passive"))
    )
    (net (code "60") (name "Net-(LED8-PadA)") (class "Default")
      (node (ref "LED8") (pin "A") (pinfunction "A_A") (pintype "passive"))
      (node (ref "R25") (pin "1") (pinfunction "1_1") (pintype "passive"))
    )
    (net (code "61") (name "Net-(LED10-PadA)") (class "Default")
      (node (ref "LED10") (pin "A") (pinfunction "A_A") (pintype "passive"))
      (node (ref "R29") (pin "1") (pinfunction "1_1") (pintype "passive"))
    )
    (net (code "62") (name "Net-(LED11-PadA)") (class "Default")
      (node (ref "LED11") (pin "A") (pinfunction "A_A") (pintype "passive"))
      (node (ref "R28") (pin "1") (pinfunction "1_1") (pintype "passive"))
    )
    (net (code "63") (name "Net-(LED12-PadA)") (class "Default")
      (node (ref "LED12") (pin "A") (pinfunction "A_A") (pintype "passive"))
      (node (ref "R27") (pin "2") (pinfunction "2_2") (pintype "passive"))
    )
    (net (code "64") (name "Net-(LSM6DS0-CAP)") (class "Default")
      (node (ref "C14") (pin "2") (pinfunction "2_2") (pintype "passive"))
      (node (ref "LSM6DS0") (pin "P$14") (pinfunction "CAP_P$14") (pintype "bidirectional"))
    )
    (net (code "65") (name "Net-(R31-Pad1)") (class "Default")
      (node (ref "R31") (pin "1") (pinfunction "1_1") (pintype "passive"))
      (node (ref "U$2") (pin "P$2_EM") (pinfunction "A_P$2_EM") (pintype "passive"))
      (node (ref "U$2") (pin "P$3-NC") (pinfunction "A_P$3-NC") (pintype "passive"))
    )
    (net (code "66") (name "Net-(R33-Pad1)") (class "Default")
      (node (ref "R33") (pin "1") (pinfunction "1_1") (pintype "passive"))
      (node (ref "U$14") (pin "P$2_EM") (pinfunction "A_P$2_EM") (pintype "passive"))
      (node (ref "U$14") (pin "P$3-NC") (pinfunction "A_P$3-NC") (pintype "passive"))
    )
    (net (code "67") (name "VCC") (class "Default")
      (node (ref "C1") (pin "1") (pinfunction "1_1") (pintype "passive"))
      (node (ref "C10") (pin "1") (pinfunction "1_1") (pintype "passive"))
      (node (ref "C2") (pin "1") (pinfunction "1_1") (pintype "passive"))
      (node (ref "C3") (pin "1") (pinfunction "1_1") (pintype "passive"))
      (node (ref "C7") (pin "+") (pinfunction "+_+") (pintype "passive"))
      (node (ref "C9") (pin "1") (pinfunction "1_1") (pintype "passive"))
      (node (ref "D1") (pin "C") (pinfunction "C_C") (pintype "passive"))
      (node (ref "IC2") (pin "1") (pinfunction "VI_1") (pintype "input"))
      (node (ref "IO1") (pin "18") (pinfunction "VM_18") (pintype "bidirectional"))
      (node (ref "IO1") (pin "19") (pinfunction "VM1_19") (pintype "bidirectional"))
      (node (ref "JP1") (pin "2") (pinfunction "2_2") (pintype "passive"))
      (node (ref "R1") (pin "1") (pinfunction "1_1") (pintype "passive"))
    )
    (net (code "68") (name "unconnected-(IO1-NFAULT-Pad16)") (class "Default")
      (node (ref "IO1") (pin "16") (pinfunction "NFAULT_16") (pintype "bidirectional"))
    )
    (net (code "69") (name "unconnected-(LSM6DS0-DRDY{slash}INT2-PadP$6)") (class "Default")
      (node (ref "LSM6DS0") (pin "P$6") (pinfunction "DRDY/INT2_P$6") (pintype "bidirectional"))
    )
    (net (code "70") (name "unconnected-(LSM6DS0-INT1-PadP$7)") (class "Default")
      (node (ref "LSM6DS0") (pin "P$7") (pinfunction "INT1_P$7") (pintype "bidirectional"))
    )
    (net (code "71") (name "unconnected-(U4A-PB10-Pad29)") (class "Default")
      (node (ref "U4") (pin "29") (pinfunction "PB10_29") (pintype "bidirectional"))
    )
    (net (code "72") (name "unconnected-(U4A-PB11-Pad30)") (class "Default")
      (node (ref "U4") (pin "30") (pinfunction "PB11_30") (pintype "bidirectional"))
    )
    (net (code "73") (name "unconnected-(U4A-PC1-Pad9)") (class "Default")
      (node (ref "U4") (pin "9") (pinfunction "PC1_9") (pintype "bidirectional"))
    )
    (net (code "74") (name "unconnected-(U4A-PC2-Pad10)") (class "Default")
      (node (ref "U4") (pin "10") (pinfunction "PC2_10") (pintype "bidirectional"))
    )
    (net (code "75") (name "unconnected-(U4A-PC3-Pad11)") (class "Default")
      (node (ref "U4") (pin "11") (pinfunction "PC3_11") (pintype "bidirectional"))
    )
    (net (code "76") (name "unconnected-(U4A-PC4-Pad24)") (class "Default")
      (node (ref "U4") (pin "24") (pinfunction "PC4_24") (pintype "bidirectional"))
    )
    (net (code "77") (name "unconnected-(U4A-PC5-Pad25)") (class "Default")
      (node (ref "U4") (pin "25") (pinfunction "PC5_25") (pintype "bidirectional"))
    )
    (net (code "78") (name "unconnected-(U4A-PC14-OSC32_IN-Pad3)") (class "Default")
      (node (ref "U4") (pin "3") (pinfunction "PC14-OSC32_IN_3") (pintype "bidirectional"))
    )
    (net (code "79") (name "unconnected-(U4A-PC15-OSC32_OUT-Pad4)") (class "Default")
      (node (ref "U4") (pin "4") (pinfunction "PC15-OSC32_OUT_4") (pintype "bidirectional"))
    )
    (net (code "80") (name "unconnected-(U4A-PF4-Pad18)") (class "Default")
      (node (ref "U4") (pin "18") (pinfunction "PF4_18") (pintype "bidirectional"))
    )
    (net (code "81") (name "unconnected-(U4B-PB3-Pad55)") (class "Default")
      (node (ref "U4") (pin "55") (pinfunction "PB3_55") (pintype "bidirectional"))
    )
    (net (code "82") (name "unconnected-(U4B-PB8-Pad61)") (class "Default")
      (node (ref "U4") (pin "61") (pinfunction "PB8_61") (pintype "bidirectional"))
    )
    (net (code "83") (name "unconnected-(U4B-PB9-Pad62)") (class "Default")
      (node (ref "U4") (pin "62") (pinfunction "PB9_62") (pintype "bidirectional"))
    )
    (net (code "84") (name "unconnected-(U4B-PC8-Pad39)") (class "Default")
      (node (ref "U4") (pin "39") (pinfunction "PC8_39") (pintype "bidirectional"))
    )
    (net (code "85") (name "unconnected-(U4B-PC9-Pad40)") (class "Default")
      (node (ref "U4") (pin "40") (pinfunction "PC9_40") (pintype "bidirectional"))
    )
    (net (code "86") (name "unconnected-(U4B-PC10-Pad51)") (class "Default")
      (node (ref "U4") (pin "51") (pinfunction "PC10_51") (pintype "bidirectional"))
    )
    (net (code "87") (name "unconnected-(U4B-PD2-Pad54)") (class "Default")
      (node (ref "U4") (pin "54") (pinfunction "PD2_54") (pintype "bidirectional"))
    )
    (net (code "88") (name "unconnected-(USER-Pad4)") (class "Default")
      (node (ref "USER") (pin "4") (pinfunction "4_4") (pintype "passive"))
    )
    (net (code "89") (name "unconnected-(X1-Pad4)") (class "Default")
      (node (ref "X1") (pin "4") (pinfunction "4_4") (pintype "passive"))
    )
  )
)
